# i2c2pwm.net
KiCad netlist of a schematic drawn in EAGLE
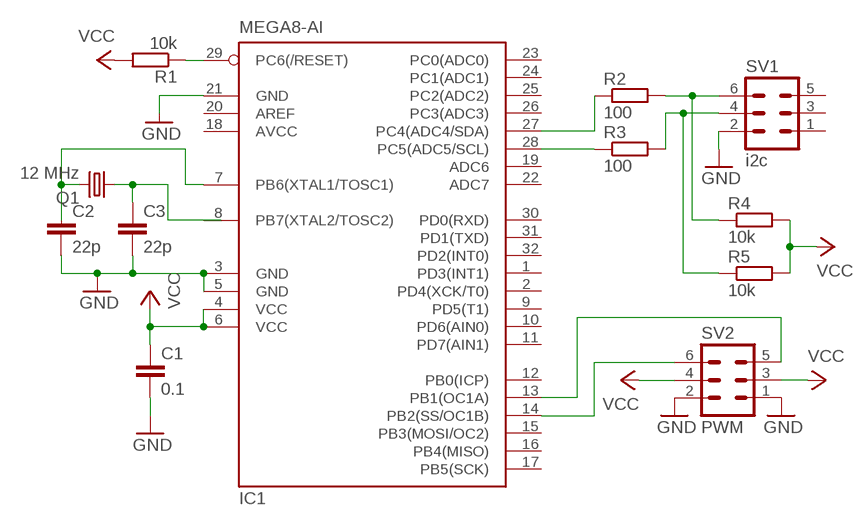
[diagram p0: schematic, sheet 1]

(export (version "E")
  (design (tool "Eeschema 10.0.6"))
  (components
    (comp (ref "C1")
      (value "0.1")
      (footprint "eagle-import:C0805K")
      (libsource (lib "eagle-import") (part "C-EUC0805K"))
    )
    (comp (ref "C2")
      (value "22p")
      (footprint "eagle-import:C0805K")
      (libsource (lib "eagle-import") (part "C-EUC0805K"))
    )
    (comp (ref "C3")
      (value "22p")
      (footprint "eagle-import:C0805K")
      (libsource (lib "eagle-import") (part "C-EUC0805K"))
    )
    (comp (ref "IC1")
      (value "MEGA8-AI")
      (footprint "eagle-import:TQFP32-08")
      (fields (field (name "MPN") "ATMEGA8-16AU"))
      (libsource (lib "eagle-import") (part "MEGA8-AI"))
    )
    (comp (ref "Q1")
      (value "12 MHz")
      (footprint "eagle-import:HC49_S")
      (libsource (lib "eagle-import") (part "CRYSTALHC49S"))
    )
    (comp (ref "R1")
      (value "10k")
      (footprint "eagle-import:R0805")
      (libsource (lib "eagle-import") (part "R-EU_R0805"))
    )
    (comp (ref "R2")
      (value "100")
      (footprint "eagle-import:R0805")
      (libsource (lib "eagle-import") (part "R-EU_R0805"))
    )
    (comp (ref "R3")
      (value "100")
      (footprint "eagle-import:R0805")
      (libsource (lib "eagle-import") (part "R-EU_R0805"))
    )
    (comp (ref "R4")
      (value "10k")
      (footprint "eagle-import:R0805")
      (libsource (lib "eagle-import") (part "R-EU_R0805"))
    )
    (comp (ref "R5")
      (value "10k")
      (footprint "eagle-import:R0805")
      (libsource (lib "eagle-import") (part "R-EU_R0805"))
    )
    (comp (ref "SV1")
      (value "i2c")
      (footprint "eagle-import:ML6")
      (libsource (lib "eagle-import") (part "ML6"))
    )
    (comp (ref "SV2")
      (value "PWM")
      (footprint "eagle-import:ML6")
      (libsource (lib "eagle-import") (part "ML6"))
    )
  )
  (nets
    (net (code "1") (name "/AVCC") (class "Default")
      (node (ref "IC1") (pin "18") (pinfunction "AVCC_18") (pintype "power_in"))
    )
    (net (code "2") (name "GND") (class "Default")
      (node (ref "C1") (pin "2") (pinfunction "2_2") (pintype "passive"))
      (node (ref "C2") (pin "2") (pinfunction "2_2") (pintype "passive"))
      (node (ref "C3") (pin "2") (pinfunction "2_2") (pintype "passive"))
      (node (ref "IC1") (pin "3") (pinfunction "GND_3") (pintype "power_in"))
      (node (ref "IC1") (pin "5") (pinfunction "GND_5") (pintype "power_in"))
      (node (ref "SV1") (pin "2") (pinfunction "2_2") (pintype "passive"))
      (node (ref "SV2") (pin "1") (pinfunction "1_1") (pintype "passive"))
      (node (ref "SV2") (pin "2") (pinfunction "2_2") (pintype "passive"))
    )
    (net (code "3") (name "Net-(C3-Pad1)") (class "Default")
      (node (ref "C3") (pin "1") (pinfunction "1_1") (pintype "passive"))
      (node (ref "Q1") (pin "1") (pinfunction "1_1") (pintype "passive"))
    )
    (net (code "4") (name "Net-(IC1-PB1(OC1A))") (class "Default")
      (node (ref "IC1") (pin "13") (pinfunction "PB1(OC1A)_13") (pintype "bidirectional"))
      (node (ref "SV2") (pin "5") (pinfunction "5_5") (pintype "passive"))
    )
    (net (code "5") (name "Net-(IC1-PB2(SS{slash}OC1B))") (class "Default")
      (node (ref "IC1") (pin "14") (pinfunction "PB2(SS/OC1B)_14") (pintype "bidirectional"))
      (node (ref "SV2") (pin "6") (pinfunction "6_6") (pintype "passive"))
    )
    (net (code "6") (name "Net-(IC1-PB6(XTAL1{slash}TOSC1))") (class "Default")
      (node (ref "IC1") (pin "7") (pinfunction "PB6(XTAL1/TOSC1)_7") (pintype "bidirectional"))
      (node (ref "Q1") (pin "2") (pinfunction "2_2") (pintype "passive"))
    )
    (net (code "7") (name "Net-(IC1-PC4(ADC4{slash}SDA))") (class "Default")
      (node (ref "IC1") (pin "27") (pinfunction "PC4(ADC4/SDA)_27") (pintype "bidirectional"))
      (node (ref "R2") (pin "1") (pinfunction "1_1") (pintype "passive"))
    )
    (net (code "8") (name "Net-(IC1-PC5(ADC5{slash}SCL))") (class "Default")
      (node (ref "IC1") (pin "28") (pinfunction "PC5(ADC5/SCL)_28") (pintype "bidirectional"))
      (node (ref "R3") (pin "1") (pinfunction "1_1") (pintype "passive"))
    )
    (net (code "9") (name "Net-(IC1-PC6({slash}RESET))") (class "Default")
      (node (ref "IC1") (pin "29") (pinfunction "PC6(/RESET)_29") (pintype "bidirectional"))
      (node (ref "R1") (pin "1") (pinfunction "1_1") (pintype "passive"))
    )
    (net (code "10") (name "Net-(R2-Pad2)") (class "Default")
      (node (ref "R2") (pin "2") (pinfunction "2_2") (pintype "passive"))
      (node (ref "R4") (pin "1") (pinfunction "1_1") (pintype "passive"))
      (node (ref "SV1") (pin "6") (pinfunction "6_6") (pintype "passive"))
    )
    (net (code "11") (name "Net-(R3-Pad2)") (class "Default")
      (node (ref "R3") (pin "2") (pinfunction "2_2") (pintype "passive"))
      (node (ref "R5") (pin "1") (pinfunction "1_1") (pintype "passive"))
      (node (ref "SV1") (pin "4") (pinfunction "4_4") (pintype "passive"))
    )
    (net (code "12") (name "VCC") (class "Default")
      (node (ref "C1") (pin "1") (pinfunction "1_1") (pintype "passive"))
      (node (ref "IC1") (pin "4") (pinfunction "VCC_4") (pintype "power_in"))
      (node (ref "IC1") (pin "6") (pinfunction "VCC_6") (pintype "power_in"))
      (node (ref "R1") (pin "2") (pinfunction "2_2") (pintype "passive"))
      (node (ref "R4") (pin "2") (pinfunction "2_2") (pintype "passive"))
      (node (ref "R5") (pin "2") (pinfunction "2_2") (pintype "passive"))
      (node (ref "SV2") (pin "3") (pinfunction "3_3") (pintype "passive"))
      (node (ref "SV2") (pin "4") (pinfunction "4_4") (pintype "passive"))
    )
    (net (code "13") (name "unconnected-(C2-Pad1)") (class "Default")
      (node (ref "C2") (pin "1") (pinfunction "1_1") (pintype "passive"))
    )
    (net (code "14") (name "unconnected-(IC1-ADC6-Pad19)") (class "Default")
      (node (ref "IC1") (pin "19") (pinfunction "ADC6_19") (pintype "bidirectional"))
    )
    (net (code "15") (name "unconnected-(IC1-ADC7-Pad22)") (class "Default")
      (node (ref "IC1") (pin "22") (pinfunction "ADC7_22") (pintype "bidirectional"))
    )
    (net (code "16") (name "unconnected-(IC1-AREF-Pad20)") (class "Default")
      (node (ref "IC1") (pin "20") (pinfunction "AREF_20") (pintype "passive"))
    )
    (net (code "17") (name "unconnected-(IC1-GND-Pad21)") (class "Default")
      (node (ref "IC1") (pin "21") (pinfunction "GND_21") (pintype "power_in"))
    )
    (net (code "18") (name "unconnected-(IC1-PB0(ICP)-Pad12)") (class "Default")
      (node (ref "IC1") (pin "12") (pinfunction "PB0(ICP)_12") (pintype "bidirectional"))
    )
    (net (code "19") (name "unconnected-(IC1-PB3(MOSI{slash}OC2)-Pad15)") (class "Default")
      (node (ref "IC1") (pin "15") (pinfunction "PB3(MOSI/OC2)_15") (pintype "bidirectional"))
    )
    (net (code "20") (name "unconnected-(IC1-PB4(MISO)-Pad16)") (class "Default")
      (node (ref "IC1") (pin "16") (pinfunction "PB4(MISO)_16") (pintype "bidirectional"))
    )
    (net (code "21") (name "unconnected-(IC1-PB5(SCK)-Pad17)") (class "Default")
      (node (ref "IC1") (pin "17") (pinfunction "PB5(SCK)_17") (pintype "bidirectional"))
    )
    (net (code "22") (name "unconnected-(IC1-PB7(XTAL2{slash}TOSC2)-Pad8)") (class "Default")
      (node (ref "IC1") (pin "8") (pinfunction "PB7(XTAL2/TOSC2)_8") (pintype "bidirectional"))
    )
    (net (code "23") (name "unconnected-(IC1-PC0(ADC0)-Pad23)") (class "Default")
      (node (ref "IC1") (pin "23") (pinfunction "PC0(ADC0)_23") (pintype "bidirectional"))
    )
    (net (code "24") (name "unconnected-(IC1-PC1(ADC1)-Pad24)") (class "Default")
      (node (ref "IC1") (pin "24") (pinfunction "PC1(ADC1)_24") (pintype "bidirectional"))
    )
    (net (code "25") (name "unconnected-(IC1-PC2(ADC2)-Pad25)") (class "Default")
      (node (ref "IC1") (pin "25") (pinfunction "PC2(ADC2)_25") (pintype "bidirectional"))
    )
    (net (code "26") (name "unconnected-(IC1-PC3(ADC3)-Pad26)") (class "Default")
      (node (ref "IC1") (pin "26") (pinfunction "PC3(ADC3)_26") (pintype "bidirectional"))
    )
    (net (code "27") (name "unconnected-(IC1-PD0(RXD)-Pad30)") (class "Default")
      (node (ref "IC1") (pin "30") (pinfunction "PD0(RXD)_30") (pintype "bidirectional"))
    )
    (net (code "28") (name "unconnected-(IC1-PD1(TXD)-Pad31)") (class "Default")
      (node (ref "IC1") (pin "31") (pinfunction "PD1(TXD)_31") (pintype "bidirectional"))
    )
    (net (code "29") (name "unconnected-(IC1-PD2(INT0)-Pad32)") (class "Default")
      (node (ref "IC1") (pin "32") (pinfunction "PD2(INT0)_32") (pintype "bidirectional"))
    )
    (net (code "30") (name "unconnected-(IC1-PD3(INT1)-Pad1)") (class "Default")
      (node (ref "IC1") (pin "1") (pinfunction "PD3(INT1)_1") (pintype "bidirectional"))
    )
    (net (code "31") (name "unconnected-(IC1-PD4(XCK{slash}T0)-Pad2)") (class "Default")
      (node (ref "IC1") (pin "2") (pinfunction "PD4(XCK/T0)_2") (pintype "bidirectional"))
    )
    (net (code "32") (name "unconnected-(IC1-PD5(T1)-Pad9)") (class "Default")
      (node (ref "IC1") (pin "9") (pinfunction "PD5(T1)_9") (pintype "bidirectional"))
    )
    (net (code "33") (name "unconnected-(IC1-PD6(AIN0)-Pad10)") (class "Default")
      (node (ref "IC1") (pin "10") (pinfunction "PD6(AIN0)_10") (pintype "bidirectional"))
    )
    (net (code "34") (name "unconnected-(IC1-PD7(AIN1)-Pad11)") (class "Default")
      (node (ref "IC1") (pin "11") (pinfunction "PD7(AIN1)_11") (pintype "bidirectional"))
    )
    (net (code "35") (name "unconnected-(SV1-Pad1)") (class "Default")
      (node (ref "SV1") (pin "1") (pinfunction "1_1") (pintype "passive"))
    )
    (net (code "36") (name "unconnected-(SV1-Pad3)") (class "Default")
      (node (ref "SV1") (pin "3") (pinfunction "3_3") (pintype "passive"))
    )
    (net (code "37") (name "unconnected-(SV1-Pad5)") (class "Default")
      (node (ref "SV1") (pin "5") (pinfunction "5_5") (pintype "passive"))
    )
  )
)
